# Quad_FC_power_V10_5.net
KiCad netlist of a schematic drawn in Altium Designer
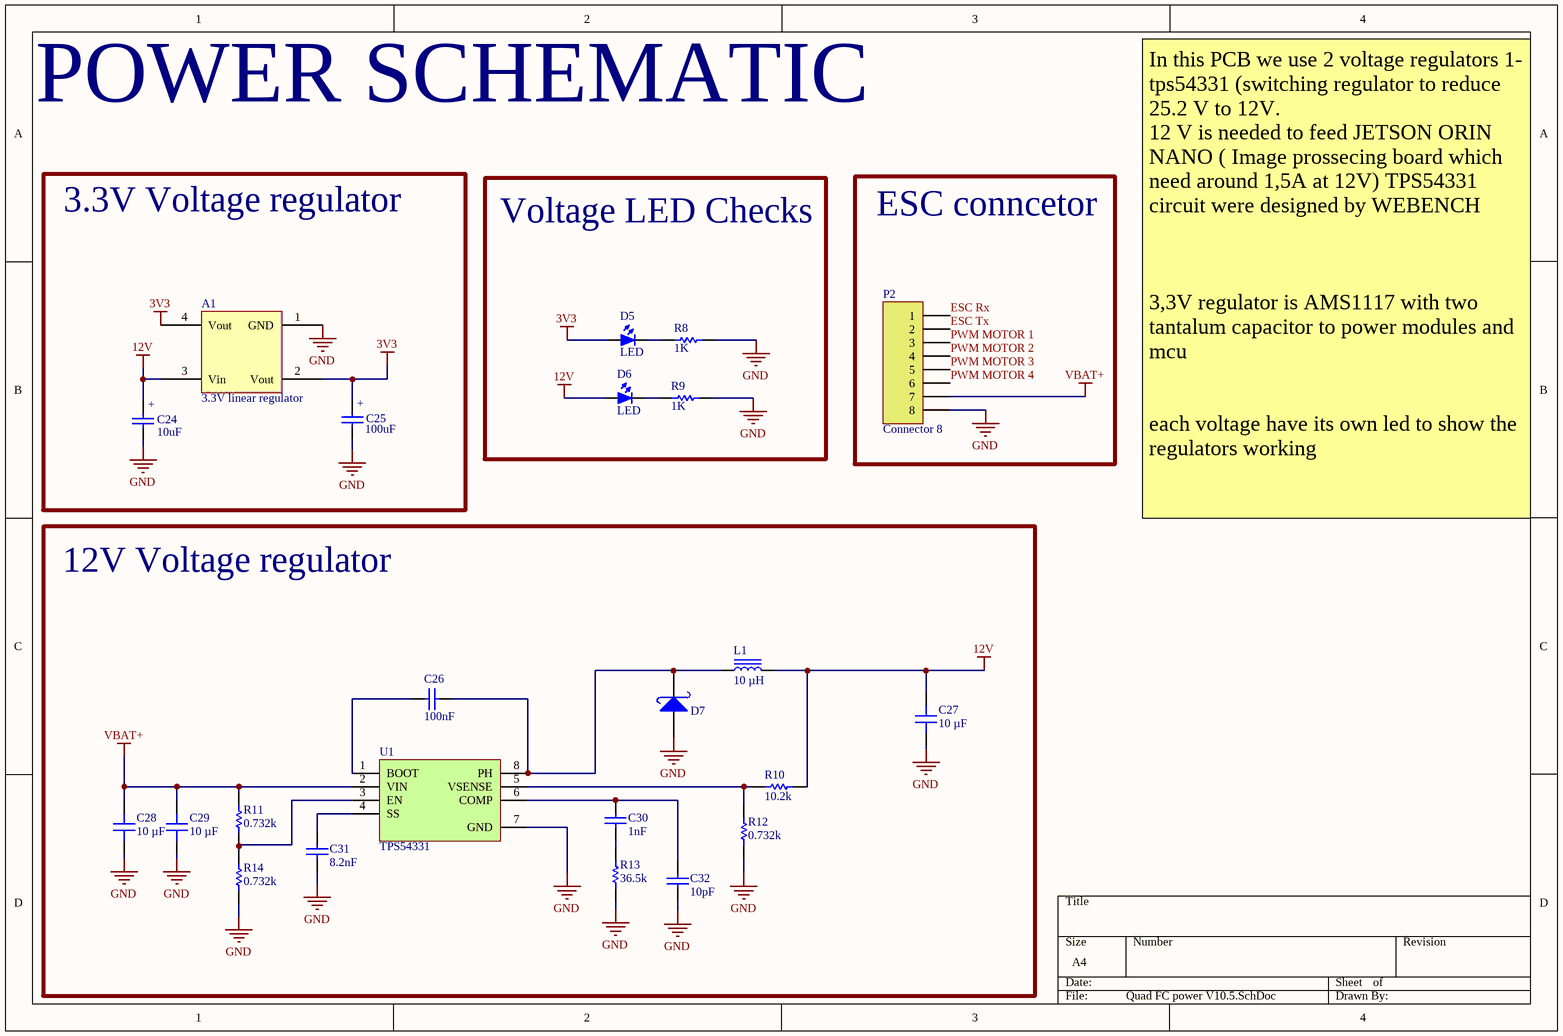
[diagram p0: Quad FC power V10.5.SchDoc]

(export (version "E")
  (design (tool "Eeschema 10.0.6"))
  (components
    (comp (ref "A1")
      (value "3.3V linear regulator")
      (footprint "SOT230P700X180-4N")
      (libsource (lib "Integrated_Library1") (part "ams1117"))
    )
    (comp (ref "C24")
      (value "10uF")
      (footprint "MY_CAP_SMD-B")
      (description "3.5X2.8MM")
      (libsource (lib "AMINLIB") (part "CAP_TANTAL_B"))
    )
    (comp (ref "C25")
      (value "100uF")
      (footprint "MY_CAP_SMD-B")
      (description "3.5X2.8MM")
      (libsource (lib "AMINLIB") (part "CAP_TANTAL_B"))
    )
    (comp (ref "C26")
      (value "100nF")
      (footprint "CAP0603")
      (description "F407VET6 Power CAP")
      (fields (field (name "DESIGNER") "Abbas Basereh"))
      (libsource (lib "2017AbbasBasereh9365731239 -ver1") (part "CAP SMD PACKAGE"))
    )
    (comp (ref "C27")
      (value "10 µF")
      (footprint "CAP 0805_2012")
      (description "CAP CER 10UF 50V X5R 0805")
      (fields
        (field (name "PART NUMBER") "GRM21BR61H106KE43K")
        (field (name "MANUFACTURER") "Murata Electronics")
      )
      (libsource (lib "Celestial Altium Library - altium_library (1)") (part "Capacitor"))
    )
    (comp (ref "C28")
      (value "10 µF")
      (footprint "CAP 0805_2012")
      (description "CAP CER 10UF 50V X5R 0805")
      (fields
        (field (name "PART NUMBER") "GRM21BR61H106KE43K")
        (field (name "MANUFACTURER") "Murata Electronics")
      )
      (libsource (lib "Celestial Altium Library - altium_library (1)") (part "Capacitor"))
    )
    (comp (ref "C29")
      (value "10 µF")
      (footprint "CAP 0805_2012")
      (description "CAP CER 10UF 50V X5R 0805")
      (fields
        (field (name "PART NUMBER") "GRM21BR61H106KE43K")
        (field (name "MANUFACTURER") "Murata Electronics")
      )
      (libsource (lib "Celestial Altium Library - altium_library (1)") (part "Capacitor"))
    )
    (comp (ref "C30")
      (value "1nF")
      (footprint "CAP0603")
      (description "F407VET6 Power CAP")
      (fields (field (name "DESIGNER") "Abbas Basereh"))
      (libsource (lib "2017AbbasBasereh9365731239 -ver1") (part "CAP SMD PACKAGE"))
    )
    (comp (ref "C31")
      (value "8.2nF")
      (footprint "CAP0603")
      (description "F407VET6 Power CAP")
      (fields (field (name "DESIGNER") "Abbas Basereh"))
      (libsource (lib "2017AbbasBasereh9365731239 -ver1") (part "CAP SMD PACKAGE"))
    )
    (comp (ref "C32")
      (value "10pF")
      (footprint "CAP0603")
      (description "F407VET6 Power CAP")
      (fields (field (name "DESIGNER") "Abbas Basereh"))
      (libsource (lib "2017AbbasBasereh9365731239 -ver1") (part "CAP SMD PACKAGE"))
    )
    (comp (ref "D5")
      (value "LED")
      (footprint "0603 - LED")
      (description "Led")
      (fields (field (name "PUBLISHER") "Altium Limited"))
      (libsource (lib "Sajad_Altium_Library") (part "LED"))
    )
    (comp (ref "D6")
      (value "LED")
      (footprint "0603 - LED")
      (description "Led")
      (fields (field (name "PUBLISHER") "Altium Limited"))
      (libsource (lib "Sajad_Altium_Library") (part "LED"))
    )
    (comp (ref "D7")
      (value "1n5822")
      (footprint "SS34:DIOM4226X244N")
      (description "Schottky Rectifiers")
      (fields
        (field (name "MANUFACTURER") "ON Semiconductor/Fairchild")
        (field (name "DESIGNER") "Abbas Basereh")
      )
      (libsource (lib "2017AbbasBasereh9365731239 -ver1") (part "1n5822 SMD"))
    )
    (comp (ref "L1")
      (value "10 µH")
      (footprint "TAIYO YUDEN NRS8030")
      (description "FIXED IND 10UH 3A 42.9 MOHM SMD")
      (fields (field (name "PART NUMBER") "NRS8030T100MJGJV") (field (name "MANUFACTURER") "Taiyo Yuden"))
      (libsource (lib "Celestial Altium Library - altium_library (1)") (part "Inductor"))
    )
    (comp (ref "P2")
      (value "Connector 8")
      (footprint "JST B8B-PH-K")
      (description "Connector, 8-Pin2.5mm")
      (fields (field (name "PUBLISHER") "Altium Limited"))
      (libsource (lib "Sajad_Altium_Library") (part "Connector1x8"))
    )
    (comp (ref "R8")
      (value "1K")
      (footprint "RES0603")
      (description "TOTAL SMD RESISTOR PACK")
      (fields (field (name "DESIGNER") "Abbas Basereh"))
      (libsource (lib "2017AbbasBasereh9365731239 -ver1") (part "RES SMD PACKAGE"))
    )
    (comp (ref "R9")
      (value "1K")
      (footprint "RES0603")
      (description "TOTAL SMD RESISTOR PACK")
      (fields (field (name "DESIGNER") "Abbas Basereh"))
      (libsource (lib "2017AbbasBasereh9365731239 -ver1") (part "RES SMD PACKAGE"))
    )
    (comp (ref "R10")
      (value "10.2k")
      (footprint "RES0603")
      (description "TOTAL SMD RESISTOR PACK")
      (fields (field (name "DESIGNER") "Abbas Basereh"))
      (libsource (lib "2017AbbasBasereh9365731239 -ver1") (part "RES SMD PACKAGE"))
    )
    (comp (ref "R11")
      (value "0.732k")
      (footprint "RES0603")
      (description "TOTAL SMD RESISTOR PACK")
      (fields (field (name "DESIGNER") "Abbas Basereh"))
      (libsource (lib "2017AbbasBasereh9365731239 -ver1") (part "RES SMD PACKAGE"))
    )
    (comp (ref "R12")
      (value "0.732k")
      (footprint "RES0603")
      (description "TOTAL SMD RESISTOR PACK")
      (fields (field (name "DESIGNER") "Abbas Basereh"))
      (libsource (lib "2017AbbasBasereh9365731239 -ver1") (part "RES SMD PACKAGE"))
    )
    (comp (ref "R13")
      (value "36.5k")
      (footprint "RES0603")
      (description "TOTAL SMD RESISTOR PACK")
      (fields (field (name "Comment") "36.5K") (field (name "DESIGNER") "Abbas Basereh"))
      (libsource (lib "2017AbbasBasereh9365731239 -ver1") (part "RES SMD PACKAGE"))
    )
    (comp (ref "R14")
      (value "0.732k")
      (footprint "RES0603")
      (description "TOTAL SMD RESISTOR PACK")
      (fields (field (name "DESIGNER") "Abbas Basereh"))
      (libsource (lib "2017AbbasBasereh9365731239 -ver1") (part "RES SMD PACKAGE"))
    )
    (comp (ref "U1")
      (value "TPS54331")
      (footprint "SO8")
      (description "DC/DC Switching Regulators 2A,28V,1MHz Step Down SWIFT DC/D;Output Voltage:0.8 V to 25 V")
      (libsource (lib "Sajad_Altium_Library") (part "TPS54331"))
    )
  )
  (nets
    (net (code "1") (name "/ESC Rx") (class "Default")
      (node (ref "P2") (pin "1") (pinfunction "1_1") (pintype "passive"))
    )
    (net (code "2") (name "/ESC Tx") (class "Default")
      (node (ref "P2") (pin "2") (pinfunction "2_2") (pintype "passive"))
    )
    (net (code "3") (name "/PWM MOTOR 1") (class "Default")
      (node (ref "P2") (pin "3") (pinfunction "3_3") (pintype "passive"))
    )
    (net (code "4") (name "/PWM MOTOR 2") (class "Default")
      (node (ref "P2") (pin "4") (pinfunction "4_4") (pintype "passive"))
    )
    (net (code "5") (name "/PWM MOTOR 3") (class "Default")
      (node (ref "P2") (pin "5") (pinfunction "5_5") (pintype "passive"))
    )
    (net (code "6") (name "/PWM MOTOR 4") (class "Default")
      (node (ref "P2") (pin "6") (pinfunction "6_6") (pintype "passive"))
    )
    (net (code "7") (name "3V3") (class "Default")
      (node (ref "A1") (pin "2") (pinfunction "Vout_2") (pintype "passive"))
      (node (ref "A1") (pin "4") (pinfunction "Vout_4") (pintype "passive"))
      (node (ref "C25") (pin "+") (pinfunction "+_+") (pintype "passive"))
      (node (ref "D5") (pin "1") (pinfunction "A_1") (pintype "passive"))
    )
    (net (code "8") (name "12V") (class "Default")
      (node (ref "A1") (pin "3") (pinfunction "Vin_3") (pintype "passive"))
      (node (ref "C24") (pin "+") (pinfunction "+_+") (pintype "passive"))
      (node (ref "C27") (pin "2") (pinfunction "2_2") (pintype "passive"))
      (node (ref "D6") (pin "1") (pinfunction "A_1") (pintype "passive"))
      (node (ref "L1") (pin "2") (pinfunction "2_2") (pintype "passive"))
      (node (ref "R10") (pin "2") (pinfunction "2_2") (pintype "passive"))
    )
    (net (code "9") (name "GND") (class "Default")
      (node (ref "A1") (pin "1") (pinfunction "GND_1") (pintype "passive"))
      (node (ref "C24") (pin "-") (pinfunction "-_-") (pintype "passive"))
      (node (ref "C25") (pin "-") (pinfunction "-_-") (pintype "passive"))
      (node (ref "C27") (pin "1") (pinfunction "1_1") (pintype "passive"))
      (node (ref "C28") (pin "1") (pinfunction "1_1") (pintype "passive"))
      (node (ref "C29") (pin "1") (pinfunction "1_1") (pintype "passive"))
      (node (ref "C31") (pin "2") (pinfunction "2_2") (pintype "passive"))
      (node (ref "C32") (pin "2") (pinfunction "2_2") (pintype "passive"))
      (node (ref "D7") (pin "1") (pinfunction "A_1") (pintype "passive"))
      (node (ref "P2") (pin "8") (pinfunction "8_8") (pintype "passive"))
      (node (ref "R12") (pin "1") (pinfunction "1_1") (pintype "passive"))
      (node (ref "R13") (pin "1") (pinfunction "1_1") (pintype "passive"))
      (node (ref "R14") (pin "1") (pinfunction "1_1") (pintype "passive"))
      (node (ref "R8") (pin "2") (pinfunction "2_2") (pintype "passive"))
      (node (ref "R9") (pin "2") (pinfunction "2_2") (pintype "passive"))
      (node (ref "U1") (pin "7") (pinfunction "GND_7") (pintype "passive"))
    )
    (net (code "10") (name "Net-(C30-Pad2)") (class "Default")
      (node (ref "C30") (pin "2") (pinfunction "2_2") (pintype "passive"))
      (node (ref "R13") (pin "2") (pinfunction "2_2") (pintype "passive"))
    )
    (net (code "11") (name "Net-(D5-K)") (class "Default")
      (node (ref "D5") (pin "2") (pinfunction "K_2") (pintype "passive"))
      (node (ref "R8") (pin "1") (pinfunction "1_1") (pintype "passive"))
    )
    (net (code "12") (name "Net-(D6-K)") (class "Default")
      (node (ref "D6") (pin "2") (pinfunction "K_2") (pintype "passive"))
      (node (ref "R9") (pin "1") (pinfunction "1_1") (pintype "passive"))
    )
    (net (code "13") (name "Net-(D7-K)") (class "Default")
      (node (ref "C26") (pin "1") (pinfunction "1_1") (pintype "passive"))
      (node (ref "D7") (pin "2") (pinfunction "K_2") (pintype "passive"))
      (node (ref "L1") (pin "1") (pinfunction "1_1") (pintype "passive"))
      (node (ref "U1") (pin "8") (pinfunction "PH_8") (pintype "open_collector"))
    )
    (net (code "14") (name "Net-(U1-BOOT)") (class "Default")
      (node (ref "C26") (pin "2") (pinfunction "2_2") (pintype "passive"))
      (node (ref "U1") (pin "1") (pinfunction "BOOT_1") (pintype "passive"))
    )
    (net (code "15") (name "Net-(U1-COMP)") (class "Default")
      (node (ref "C30") (pin "1") (pinfunction "1_1") (pintype "passive"))
      (node (ref "C32") (pin "1") (pinfunction "1_1") (pintype "passive"))
      (node (ref "U1") (pin "6") (pinfunction "COMP_6") (pintype "power_in"))
    )
    (net (code "16") (name "Net-(U1-EN)") (class "Default")
      (node (ref "R11") (pin "1") (pinfunction "1_1") (pintype "passive"))
      (node (ref "R14") (pin "2") (pinfunction "2_2") (pintype "passive"))
      (node (ref "U1") (pin "3") (pinfunction "EN_3") (pintype "passive"))
    )
    (net (code "17") (name "Net-(U1-SS)") (class "Default")
      (node (ref "C31") (pin "1") (pinfunction "1_1") (pintype "passive"))
      (node (ref "U1") (pin "4") (pinfunction "SS_4") (pintype "power_in"))
    )
    (net (code "18") (name "Net-(U1-VSENSE)") (class "Default")
      (node (ref "R10") (pin "1") (pinfunction "1_1") (pintype "passive"))
      (node (ref "R12") (pin "2") (pinfunction "2_2") (pintype "passive"))
      (node (ref "U1") (pin "5") (pinfunction "VSENSE_5") (pintype "passive"))
    )
    (net (code "19") (name "VBAT+") (class "Default")
      (node (ref "C28") (pin "2") (pinfunction "2_2") (pintype "passive"))
      (node (ref "C29") (pin "2") (pinfunction "2_2") (pintype "passive"))
      (node (ref "P2") (pin "7") (pinfunction "7_7") (pintype "passive"))
      (node (ref "R11") (pin "2") (pinfunction "2_2") (pintype "passive"))
      (node (ref "U1") (pin "2") (pinfunction "VIN_2") (pintype "passive"))
    )
  )
)
